# PART1.net
KiCad netlist of a schematic drawn in Altium Designer
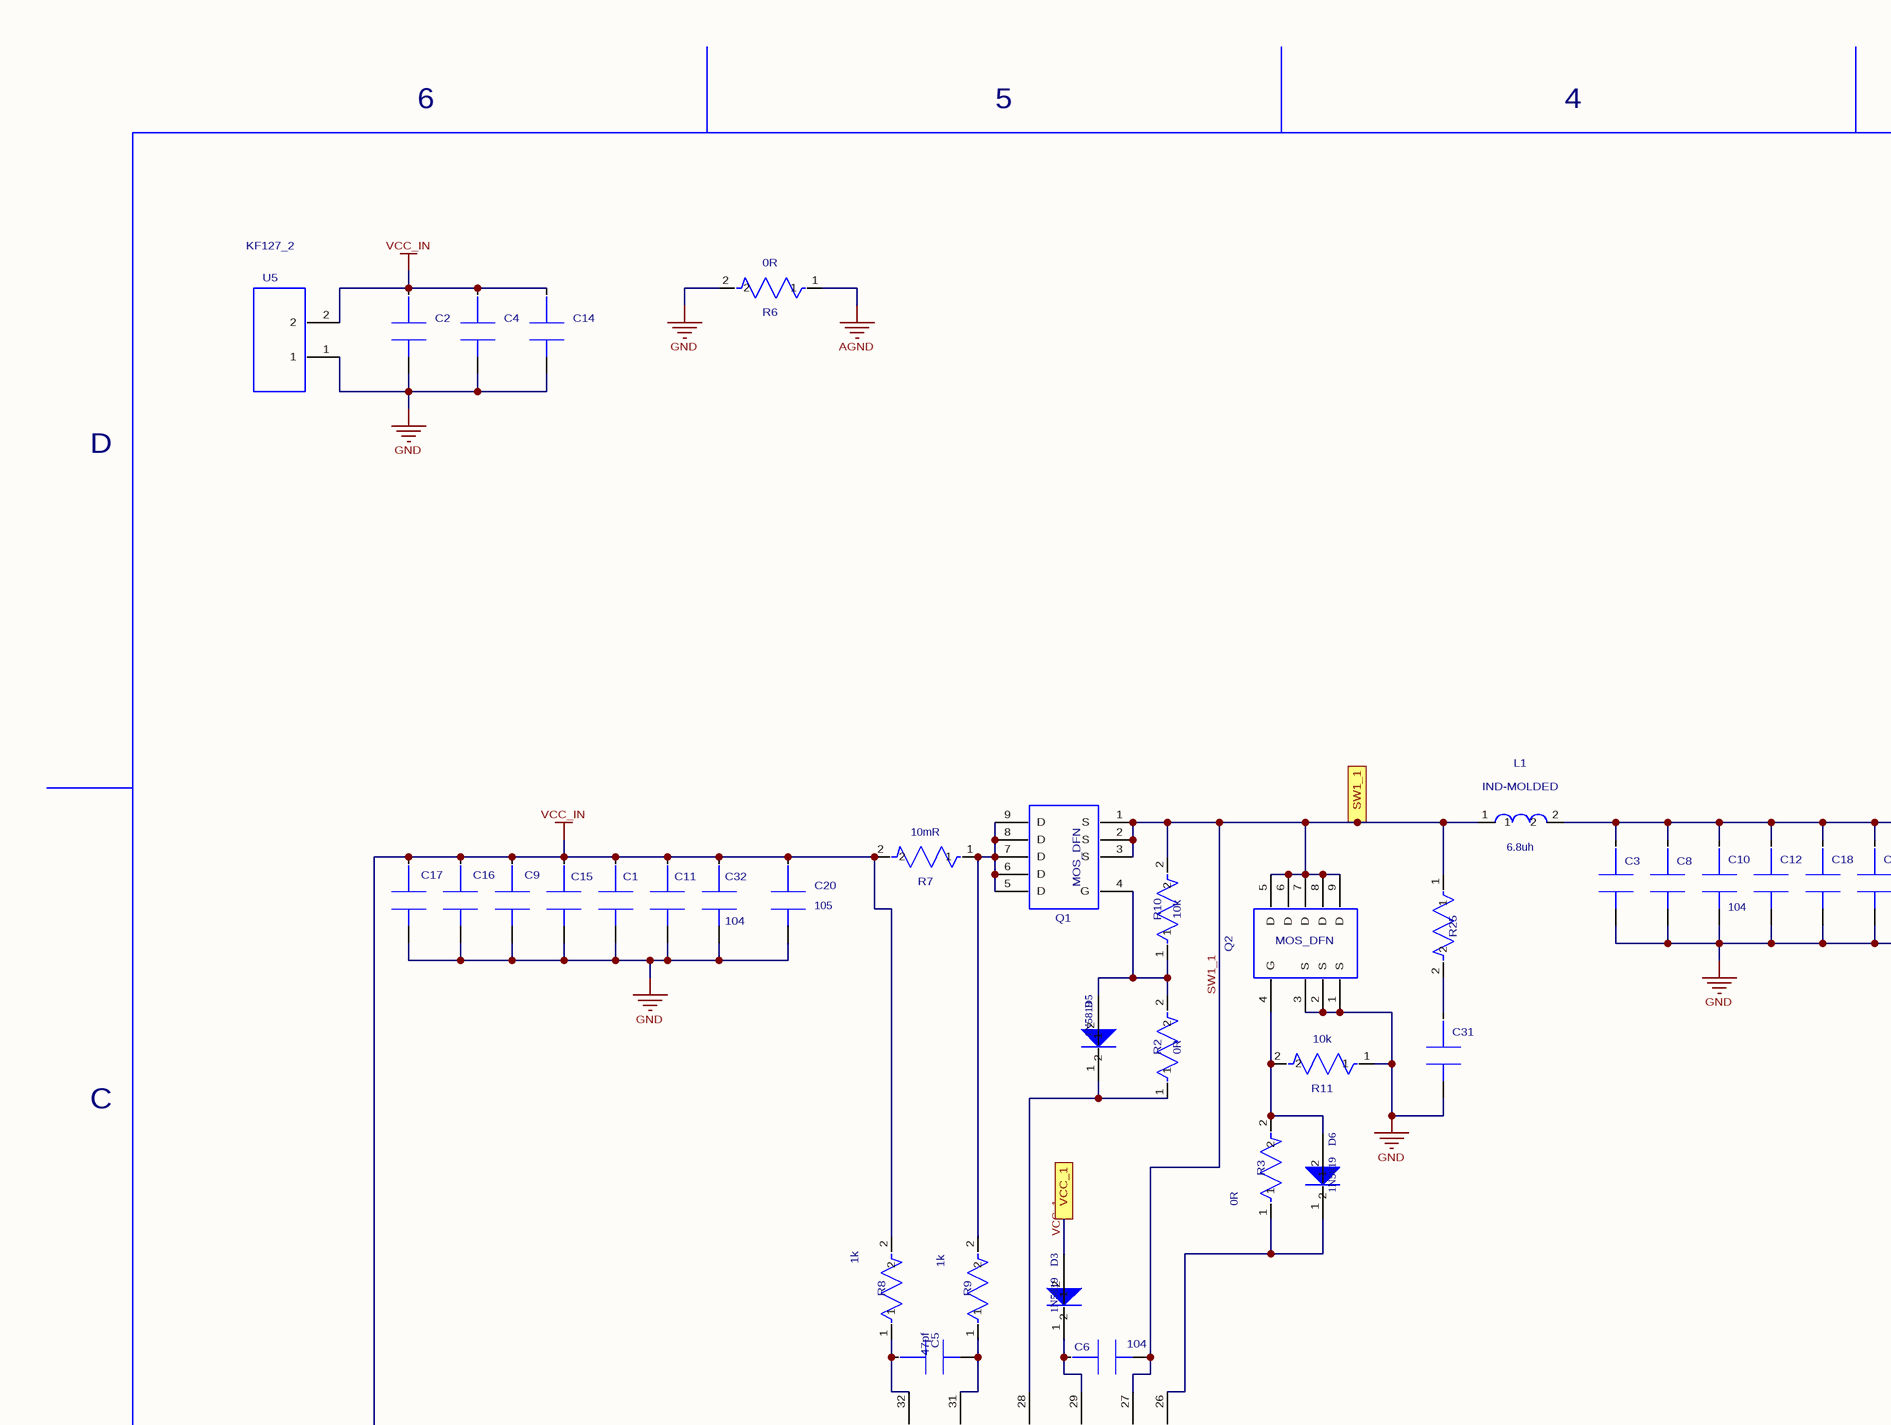
[diagram p0: PART1.SchDoc, top left]
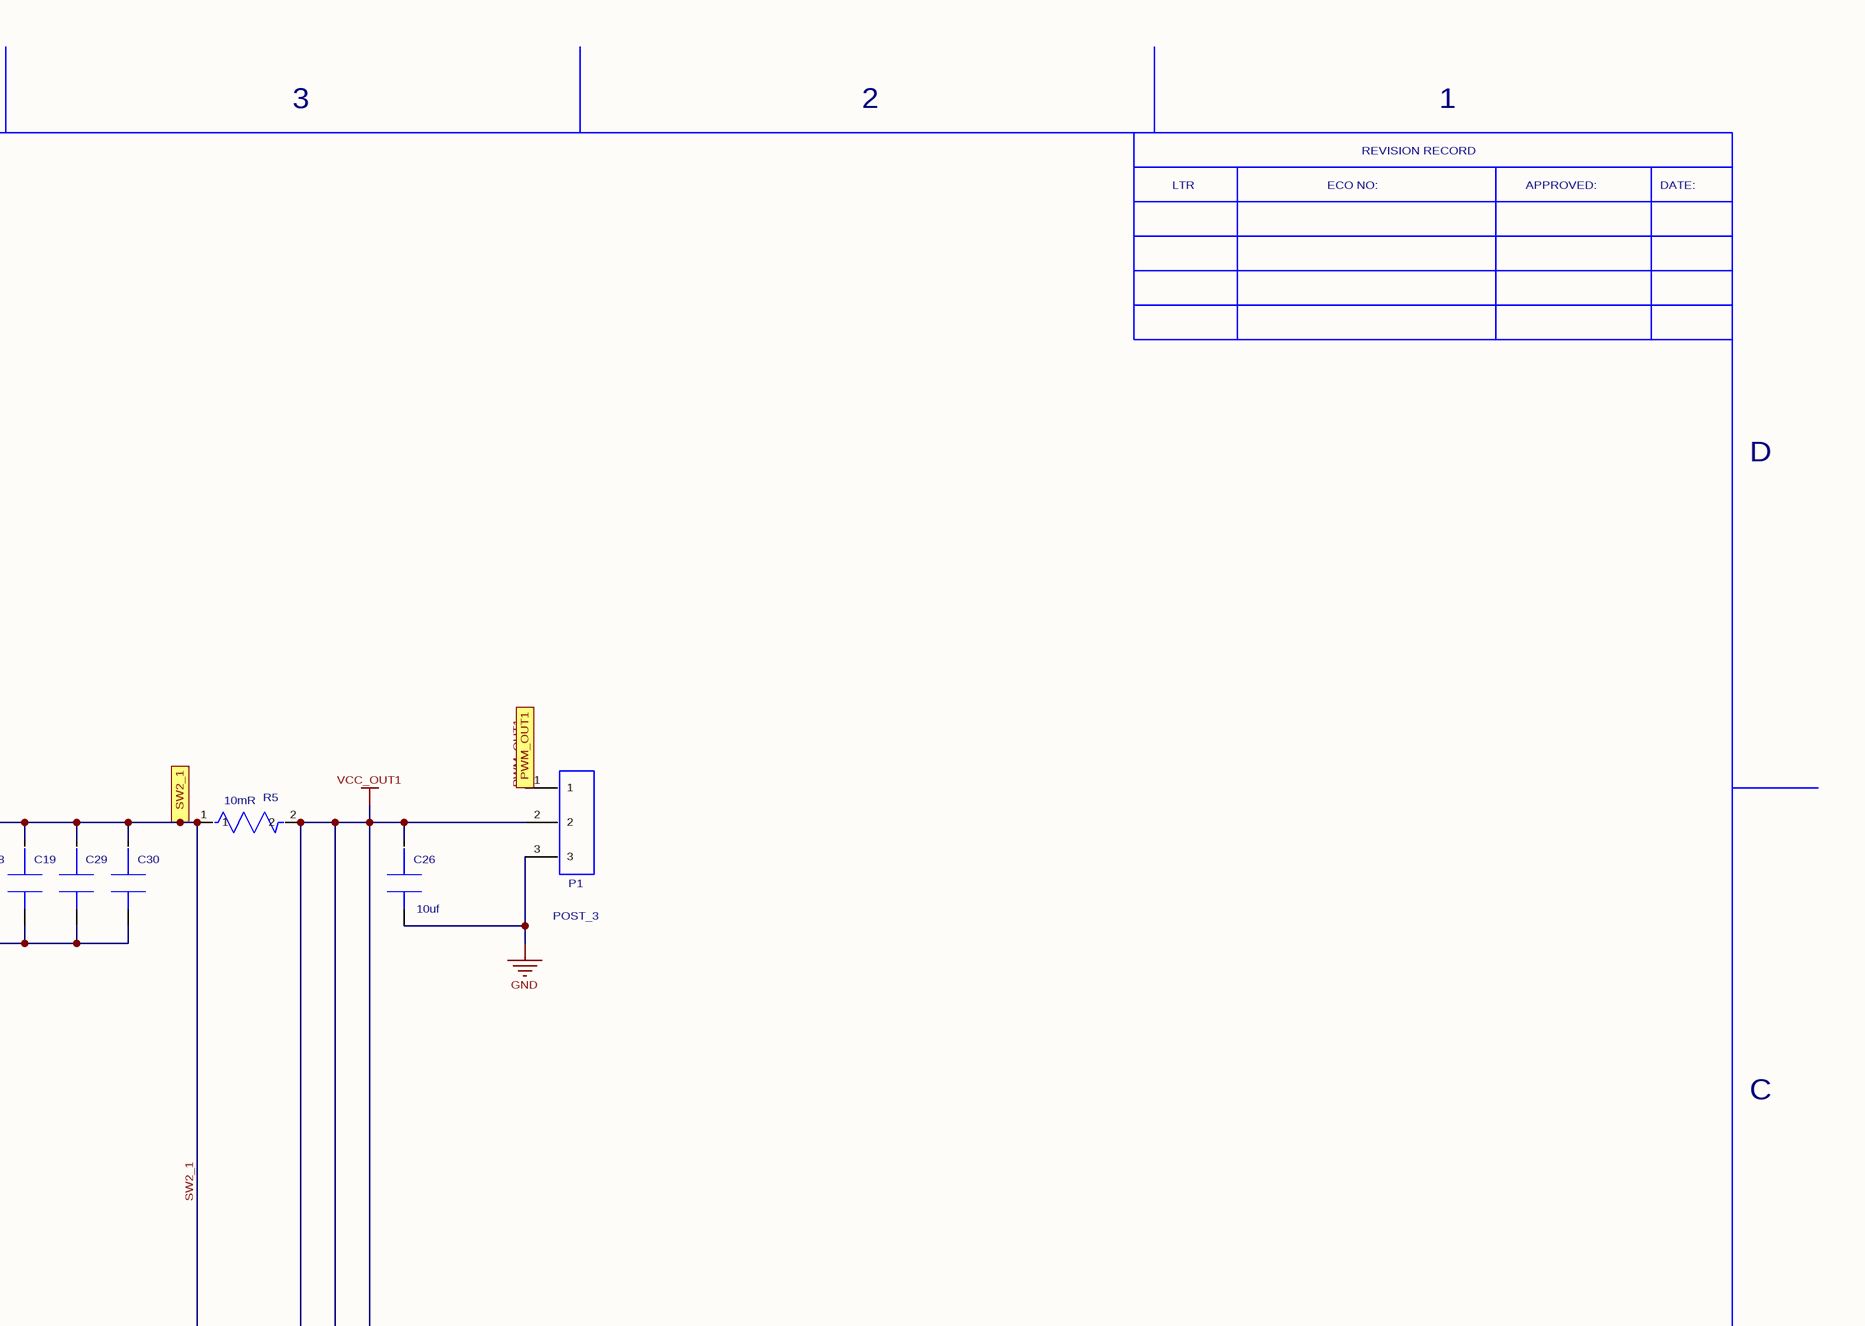
[diagram p1: PART1.SchDoc, top right]
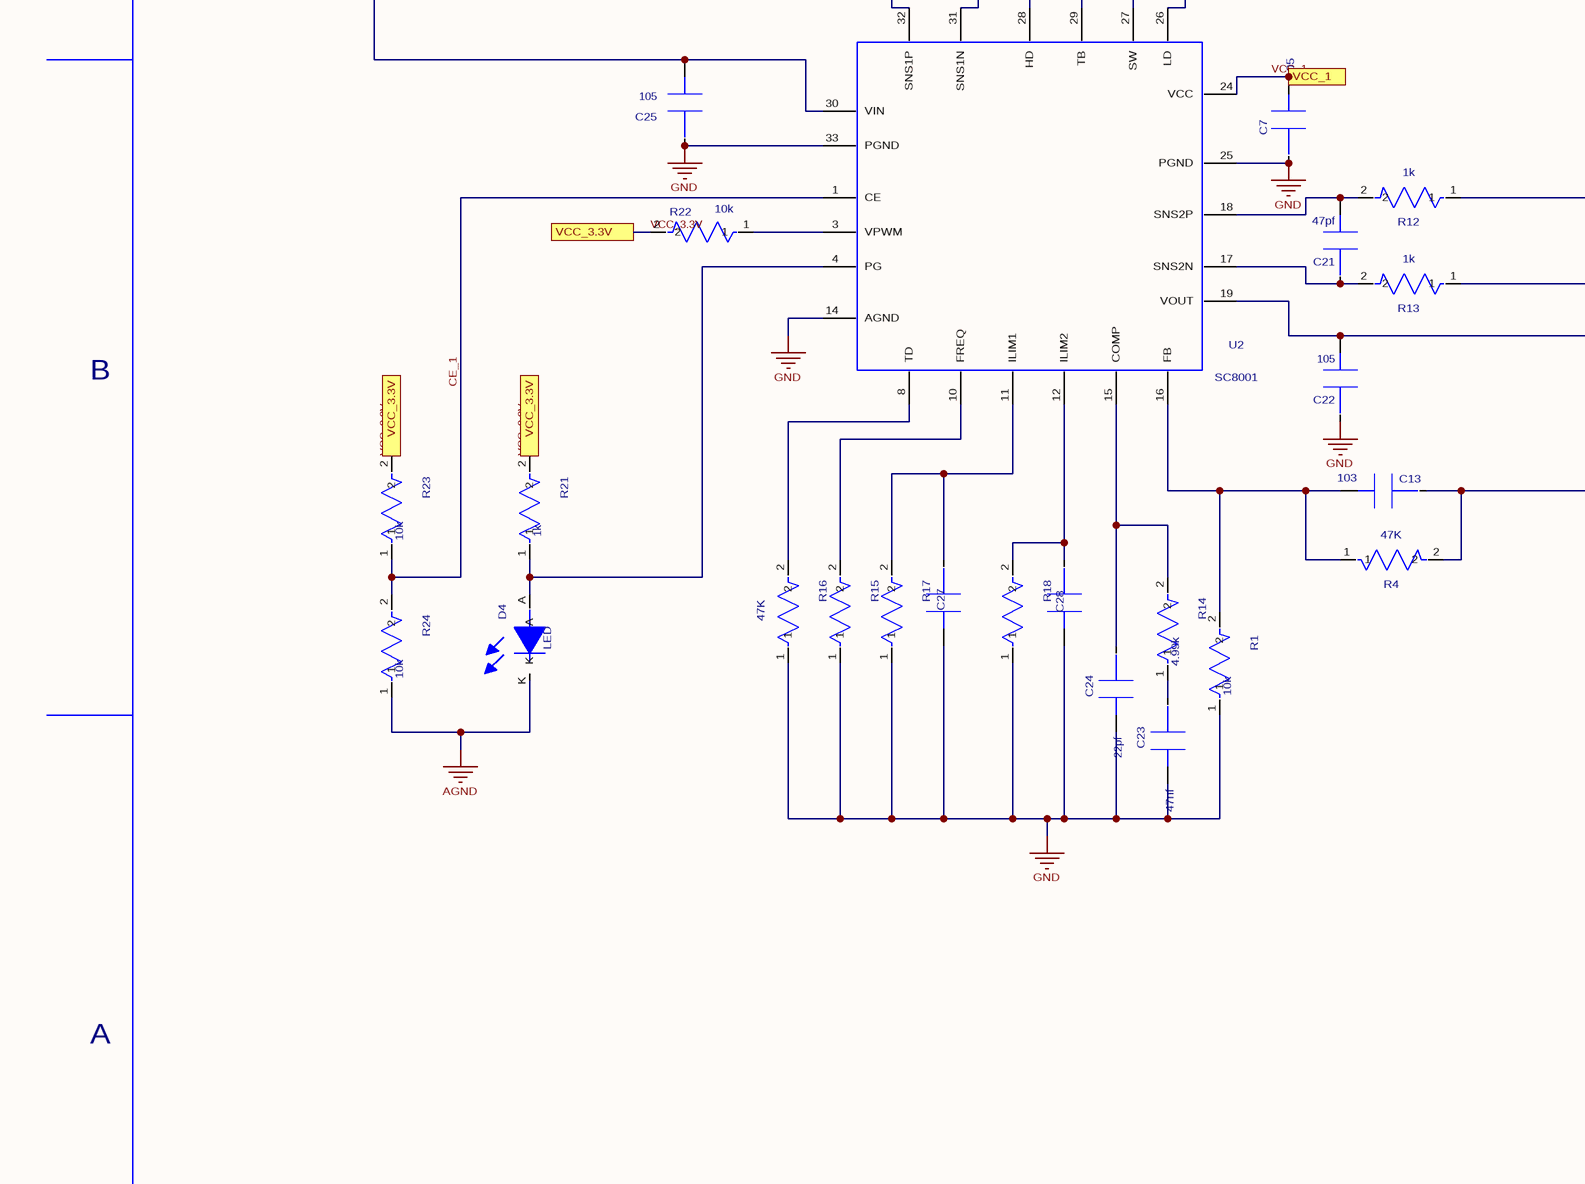
[diagram p2: PART1.SchDoc, bottom left]
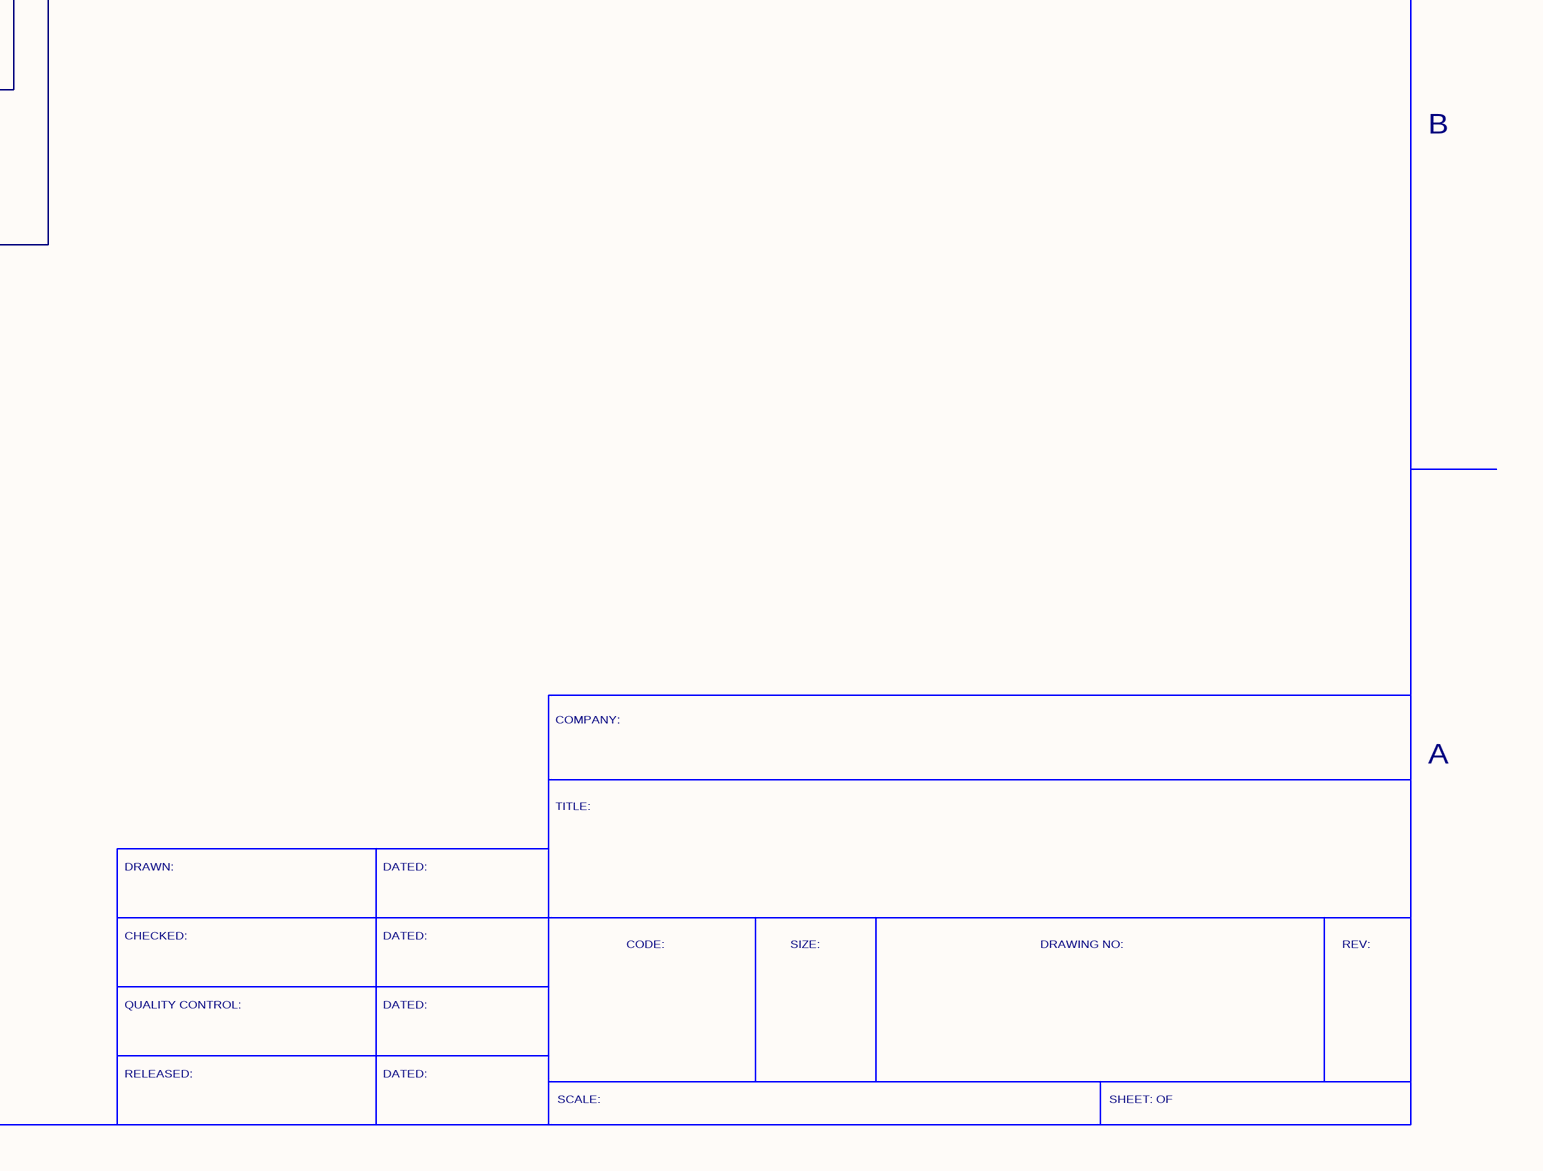
[diagram p3: PART1.SchDoc, bottom right]

(export (version "E")
  (design (tool "Eeschema 10.0.6"))
  (components
    (comp (ref "C1")
      (value "CAP-CFR04R-C")
      (footprint "1210C")
      (description "RADIAL FILM CAPACITOR, MIL-SPEC SIZE CFR04R SIZE 'C'")
      (fields (field (name "TOLERANCE") "???") (field (name "PART NUMBER") "TBD"))
      (libsource (lib "*") (part "CAP-CFR04R-C"))
    )
    (comp (ref "C2")
      (value "CAP-AE6.3")
      (footprint "CM_E(8_10.2)")
      (description "ALUMINUM ELECTROLYTIC CAP.")
      (libsource (lib "*") (part "CAP-AE6.3"))
    )
    (comp (ref "C3")
      (value "CAP-AE6.3")
      (footprint "CC6.56.5")
      (description "ALUMINUM ELECTROLYTIC CAP.")
      (libsource (lib "*") (part "CAP-AE6.3"))
    )
    (comp (ref "C4")
      (value "CAP-AE6.3")
      (footprint "CM_E(8_10.2)")
      (description "ALUMINUM ELECTROLYTIC CAP.")
      (libsource (lib "*") (part "CAP-AE6.3"))
    )
    (comp (ref "C5")
      (value "47pf")
      (footprint "0603C")
      (description "RADIAL FILM CAPACITOR, MIL-SPEC SIZE CFR04R SIZE 'C'")
      (fields (field (name "TOLERANCE") "???") (field (name "PART NUMBER") "TBD"))
      (libsource (lib "*") (part "CAP-CFR04R-C"))
    )
    (comp (ref "C6")
      (value "104")
      (footprint "0805C")
      (description "RADIAL FILM CAPACITOR, MIL-SPEC SIZE CFR04R SIZE 'C'")
      (fields (field (name "TOLERANCE") "???") (field (name "PART NUMBER") "TBD"))
      (libsource (lib "*") (part "CAP-CFR04R-C"))
    )
    (comp (ref "C7")
      (value "105")
      (footprint "0805C")
      (description "RADIAL FILM CAPACITOR, MIL-SPEC SIZE CFR04R SIZE 'C'")
      (fields (field (name "TOLERANCE") "???") (field (name "PART NUMBER") "TBD"))
      (libsource (lib "*") (part "CAP-CFR04R-C"))
    )
    (comp (ref "C8")
      (value "CAP-AE6.3")
      (footprint "CC6.56.5")
      (description "ALUMINUM ELECTROLYTIC CAP.")
      (libsource (lib "*") (part "CAP-AE6.3"))
    )
    (comp (ref "C9")
      (value "CAP-CFR04R-C")
      (footprint "1210C")
      (description "RADIAL FILM CAPACITOR, MIL-SPEC SIZE CFR04R SIZE 'C'")
      (fields (field (name "TOLERANCE") "???") (field (name "PART NUMBER") "TBD"))
      (libsource (lib "*") (part "CAP-CFR04R-C"))
    )
    (comp (ref "C10")
      (value "104")
      (footprint "1206C")
      (description "RADIAL FILM CAPACITOR, MIL-SPEC SIZE CFR04R SIZE 'C'")
      (fields (field (name "TOLERANCE") "???") (field (name "PART NUMBER") "TBD"))
      (libsource (lib "*") (part "CAP-CFR04R-C"))
    )
    (comp (ref "C11")
      (value "CAP-CFR04R-C")
      (footprint "1210C")
      (description "RADIAL FILM CAPACITOR, MIL-SPEC SIZE CFR04R SIZE 'C'")
      (fields (field (name "TOLERANCE") "???") (field (name "PART NUMBER") "TBD"))
      (libsource (lib "*") (part "CAP-CFR04R-C"))
    )
    (comp (ref "C12")
      (value "CAP-CFR04R-C")
      (footprint "1206C")
      (description "RADIAL FILM CAPACITOR, MIL-SPEC SIZE CFR04R SIZE 'C'")
      (fields (field (name "TOLERANCE") "???") (field (name "PART NUMBER") "TBD"))
      (libsource (lib "*") (part "CAP-CFR04R-C"))
    )
    (comp (ref "C13")
      (value "103")
      (footprint "0603C")
      (description "RADIAL FILM CAPACITOR, MIL-SPEC SIZE CFR04R SIZE 'C'")
      (fields (field (name "TOLERANCE") "???") (field (name "PART NUMBER") "TBD"))
      (libsource (lib "*") (part "CAP-CFR04R-C"))
    )
    (comp (ref "C14")
      (value "CAP-AE6.3")
      (footprint "CM_E(8_10.2)")
      (description "ALUMINUM ELECTROLYTIC CAP.")
      (libsource (lib "*") (part "CAP-AE6.3"))
    )
    (comp (ref "C15")
      (value "CAP-CFR04R-C")
      (footprint "1210C")
      (description "RADIAL FILM CAPACITOR, MIL-SPEC SIZE CFR04R SIZE 'C'")
      (fields (field (name "TOLERANCE") "???") (field (name "PART NUMBER") "TBD"))
      (libsource (lib "*") (part "CAP-CFR04R-C"))
    )
    (comp (ref "C16")
      (value "CAP-CFR04R-C")
      (footprint "1206C")
      (description "RADIAL FILM CAPACITOR, MIL-SPEC SIZE CFR04R SIZE 'C'")
      (fields (field (name "TOLERANCE") "???") (field (name "PART NUMBER") "TBD"))
      (libsource (lib "*") (part "CAP-CFR04R-C"))
    )
    (comp (ref "C17")
      (value "CAP-CFR04R-C")
      (footprint "1210C")
      (description "RADIAL FILM CAPACITOR, MIL-SPEC SIZE CFR04R SIZE 'C'")
      (fields (field (name "TOLERANCE") "???") (field (name "PART NUMBER") "TBD"))
      (libsource (lib "*") (part "CAP-CFR04R-C"))
    )
    (comp (ref "C18")
      (value "CAP-CFR04R-C")
      (footprint "1206C")
      (description "RADIAL FILM CAPACITOR, MIL-SPEC SIZE CFR04R SIZE 'C'")
      (fields (field (name "TOLERANCE") "???") (field (name "PART NUMBER") "TBD"))
      (libsource (lib "*") (part "CAP-CFR04R-C"))
    )
    (comp (ref "C19")
      (value "CAP-CFR04R-C")
      (footprint "1206C")
      (description "RADIAL FILM CAPACITOR, MIL-SPEC SIZE CFR04R SIZE 'C'")
      (fields (field (name "TOLERANCE") "???") (field (name "PART NUMBER") "TBD"))
      (libsource (lib "*") (part "CAP-CFR04R-C"))
    )
    (comp (ref "C20")
      (value "105")
      (footprint "0805C")
      (description "RADIAL FILM CAPACITOR, MIL-SPEC SIZE CFR04R SIZE 'C'")
      (fields (field (name "TOLERANCE") "???") (field (name "PART NUMBER") "TBD"))
      (libsource (lib "*") (part "CAP-CFR04R-C"))
    )
    (comp (ref "C21")
      (value "47pf")
      (footprint "0603C")
      (description "RADIAL FILM CAPACITOR, MIL-SPEC SIZE CFR04R SIZE 'C'")
      (fields (field (name "TOLERANCE") "???") (field (name "PART NUMBER") "TBD"))
      (libsource (lib "*") (part "CAP-CFR04R-C"))
    )
    (comp (ref "C22")
      (value "105")
      (footprint "0805C")
      (description "RADIAL FILM CAPACITOR, MIL-SPEC SIZE CFR04R SIZE 'C'")
      (fields (field (name "TOLERANCE") "???") (field (name "PART NUMBER") "TBD"))
      (libsource (lib "*") (part "CAP-CFR04R-C"))
    )
    (comp (ref "C23")
      (value "47nf")
      (footprint "0603C")
      (description "RADIAL FILM CAPACITOR, MIL-SPEC SIZE CFR04R SIZE 'C'")
      (fields (field (name "TOLERANCE") "???") (field (name "PART NUMBER") "TBD"))
      (libsource (lib "*") (part "CAP-CFR04R-C"))
    )
    (comp (ref "C24")
      (value "22pf")
      (footprint "0603C")
      (description "RADIAL FILM CAPACITOR, MIL-SPEC SIZE CFR04R SIZE 'C'")
      (fields (field (name "TOLERANCE") "???") (field (name "PART NUMBER") "TBD"))
      (libsource (lib "*") (part "CAP-CFR04R-C"))
    )
    (comp (ref "C25")
      (value "105")
      (footprint "0805C")
      (description "RADIAL FILM CAPACITOR, MIL-SPEC SIZE CFR04R SIZE 'C'")
      (fields (field (name "TOLERANCE") "???") (field (name "PART NUMBER") "TBD"))
      (libsource (lib "*") (part "CAP-CFR04R-C"))
    )
    (comp (ref "C26")
      (value "10uf")
      (footprint "1206C")
      (description "RADIAL FILM CAPACITOR, MIL-SPEC SIZE CFR04R SIZE 'C'")
      (fields (field (name "TOLERANCE") "???") (field (name "PART NUMBER") "TBD"))
      (libsource (lib "*") (part "CAP-CFR04R-C"))
    )
    (comp (ref "C27")
      (value "CAP-CFR04R-C")
      (footprint "0603C")
      (description "RADIAL FILM CAPACITOR, MIL-SPEC SIZE CFR04R SIZE 'C'")
      (fields (field (name "TOLERANCE") "???") (field (name "PART NUMBER") "TBD"))
      (libsource (lib "*") (part "CAP-CFR04R-C"))
    )
    (comp (ref "C28")
      (value "CAP-CFR04R-C")
      (footprint "0603C")
      (description "RADIAL FILM CAPACITOR, MIL-SPEC SIZE CFR04R SIZE 'C'")
      (fields (field (name "TOLERANCE") "???") (field (name "PART NUMBER") "TBD"))
      (libsource (lib "*") (part "CAP-CFR04R-C"))
    )
    (comp (ref "C29")
      (value "CAP-CFR04R-C")
      (footprint "1206C")
      (description "RADIAL FILM CAPACITOR, MIL-SPEC SIZE CFR04R SIZE 'C'")
      (fields (field (name "TOLERANCE") "???") (field (name "PART NUMBER") "TBD"))
      (libsource (lib "*") (part "CAP-CFR04R-C"))
    )
    (comp (ref "C30")
      (value "CAP-CFR04R-C")
      (footprint "1206C")
      (description "RADIAL FILM CAPACITOR, MIL-SPEC SIZE CFR04R SIZE 'C'")
      (fields (field (name "TOLERANCE") "???") (field (name "PART NUMBER") "TBD"))
      (libsource (lib "*") (part "CAP-CFR04R-C"))
    )
    (comp (ref "C31")
      (value "CAP-CFR04R-C")
      (footprint "0805C")
      (description "RADIAL FILM CAPACITOR, MIL-SPEC SIZE CFR04R SIZE 'C'")
      (fields (field (name "TOLERANCE") "???") (field (name "PART NUMBER") "TBD"))
      (libsource (lib "*") (part "CAP-CFR04R-C"))
    )
    (comp (ref "C32")
      (value "104")
      (footprint "0805C")
      (description "RADIAL FILM CAPACITOR, MIL-SPEC SIZE CFR04R SIZE 'C'")
      (fields (field (name "TOLERANCE") "???") (field (name "PART NUMBER") "TBD"))
      (libsource (lib "*") (part "CAP-CFR04R-C"))
    )
    (comp (ref "D3")
      (value "1N5819")
      (footprint "SOD-123_L2.8-W1.8-LS3.7-RD")
      (description "High Conductance Fast Diode")
      (fields (field (name "PUBLISHER") "Altium Limited"))
      (libsource (lib "*") (part "DIODE_1N4148"))
    )
    (comp (ref "D4")
      (value "LED")
      (footprint "0805D")
      (description "LIGHT EMITTING DIODE")
      (libsource (lib "*") (part "LED"))
    )
    (comp (ref "D5")
      (value "1N5819")
      (footprint "SOD-123_L2.8-W1.8-LS3.7-RD")
      (description "High Conductance Fast Diode")
      (fields (field (name "PUBLISHER") "Altium Limited"))
      (libsource (lib "*") (part "DIODE_1N4148"))
    )
    (comp (ref "D6")
      (value "1N5819")
      (footprint "SOD-123_L2.8-W1.8-LS3.7-RD")
      (description "High Conductance Fast Diode")
      (fields (field (name "PUBLISHER") "Altium Limited"))
      (libsource (lib "*") (part "DIODE_1N4148"))
    )
    (comp (ref "L1")
      (value "IND-MOLDED")
      (footprint "1040L")
      (description "MOLDED INDUCTOR, 0.5\" PIN SPACING")
      (fields (field (name "ALTIUM_VALUE") "6.8uh"))
      (libsource (lib "*") (part "IND-MOLDED"))
    )
    (comp (ref "P1") (value "POST_3") (footprint "POST_3") (libsource (lib "*") (part "POST_3")))
    (comp (ref "Q1") (value "MOS_DFN") (footprint "DFN-8_5X6") (libsource (lib "*") (part "MOS_DFN")))
    (comp (ref "Q2") (value "MOS_DFN") (footprint "DFN-8_5X6") (libsource (lib "*") (part "MOS_DFN")))
    (comp (ref "R1")
      (value "10k")
      (footprint "0603R")
      (description "WIRE WOUND RESISTOR 3.4 X 7.05 MM")
      (fields (field (name "Comment") "RES-WR1"))
      (libsource (lib "*") (part "RES-WR1"))
    )
    (comp (ref "R2")
      (value "0R")
      (footprint "0603R")
      (description "WIRE WOUND RESISTOR 3.4 X 7.05 MM")
      (fields (field (name "Comment") "RES-WR1"))
      (libsource (lib "*") (part "RES-WR1"))
    )
    (comp (ref "R3")
      (value "0R")
      (footprint "0603R")
      (description "WIRE WOUND RESISTOR 3.4 X 7.05 MM")
      (fields (field (name "Comment") "RES-WR1"))
      (libsource (lib "*") (part "RES-WR1"))
    )
    (comp (ref "R4")
      (value "47K")
      (footprint "0603R")
      (description "WIRE WOUND RESISTOR 3.4 X 7.05 MM")
      (fields (field (name "Comment") "RES-WR1"))
      (libsource (lib "*") (part "RES-WR1"))
    )
    (comp (ref "R5")
      (value "10mR")
      (footprint "1206C")
      (description "WIRE WOUND RESISTOR 3.4 X 7.05 MM")
      (fields (field (name "Comment") "RES-WR1"))
      (libsource (lib "*") (part "RES-WR1"))
    )
    (comp (ref "R6")
      (value "0R")
      (footprint "1206C")
      (description "WIRE WOUND RESISTOR 3.4 X 7.05 MM")
      (fields (field (name "Comment") "RES-WR1"))
      (libsource (lib "*") (part "RES-WR1"))
    )
    (comp (ref "R7")
      (value "10mR")
      (footprint "1206C")
      (description "WIRE WOUND RESISTOR 3.4 X 7.05 MM")
      (fields (field (name "Comment") "RES-WR1"))
      (libsource (lib "*") (part "RES-WR1"))
    )
    (comp (ref "R8")
      (value "1k")
      (footprint "0603R")
      (description "WIRE WOUND RESISTOR 3.4 X 7.05 MM")
      (fields (field (name "Comment") "RES-WR1"))
      (libsource (lib "*") (part "RES-WR1"))
    )
    (comp (ref "R9")
      (value "1k")
      (footprint "0603R")
      (description "WIRE WOUND RESISTOR 3.4 X 7.05 MM")
      (fields (field (name "Comment") "RES-WR1"))
      (libsource (lib "*") (part "RES-WR1"))
    )
    (comp (ref "R10")
      (value "10k")
      (footprint "0603R")
      (description "WIRE WOUND RESISTOR 3.4 X 7.05 MM")
      (fields (field (name "Comment") "RES-WR1"))
      (libsource (lib "*") (part "RES-WR1"))
    )
    (comp (ref "R11")
      (value "10k")
      (footprint "0603R")
      (description "WIRE WOUND RESISTOR 3.4 X 7.05 MM")
      (fields (field (name "Comment") "RES-WR1"))
      (libsource (lib "*") (part "RES-WR1"))
    )
    (comp (ref "R12")
      (value "1k")
      (footprint "0603R")
      (description "WIRE WOUND RESISTOR 3.4 X 7.05 MM")
      (fields (field (name "Comment") "RES-WR1"))
      (libsource (lib "*") (part "RES-WR1"))
    )
    (comp (ref "R13")
      (value "1k")
      (footprint "0603R")
      (description "WIRE WOUND RESISTOR 3.4 X 7.05 MM")
      (fields (field (name "Comment") "RES-WR1"))
      (libsource (lib "*") (part "RES-WR1"))
    )
    (comp (ref "R14")
      (value "4.99k")
      (footprint "0603R")
      (description "WIRE WOUND RESISTOR 3.4 X 7.05 MM")
      (fields (field (name "Comment") "RES-WR1"))
      (libsource (lib "*") (part "RES-WR1"))
    )
    (comp (ref "R15")
      (value "RES-WR1")
      (footprint "0603R")
      (description "WIRE WOUND RESISTOR 3.4 X 7.05 MM")
      (libsource (lib "*") (part "RES-WR1"))
    )
    (comp (ref "R16")
      (value "47K")
      (footprint "0603R")
      (description "WIRE WOUND RESISTOR 3.4 X 7.05 MM")
      (libsource (lib "*") (part "RES-WR1"))
    )
    (comp (ref "R17")
      (value "RES-WR1")
      (footprint "0603R")
      (description "WIRE WOUND RESISTOR 3.4 X 7.05 MM")
      (libsource (lib "*") (part "RES-WR1"))
    )
    (comp (ref "R18")
      (value "39k")
      (footprint "0603R")
      (description "WIRE WOUND RESISTOR 3.4 X 7.05 MM")
      (libsource (lib "*") (part "RES-WR1"))
    )
    (comp (ref "R21")
      (value "1k")
      (footprint "0805R")
      (description "WIRE WOUND RESISTOR 3.4 X 7.05 MM")
      (fields (field (name "Comment") "RES-WR1"))
      (libsource (lib "*") (part "RES-WR1"))
    )
    (comp (ref "R22")
      (value "10k")
      (footprint "0805R")
      (description "WIRE WOUND RESISTOR 3.4 X 7.05 MM")
      (fields (field (name "Comment") "RES-WR1"))
      (libsource (lib "*") (part "RES-WR1"))
    )
    (comp (ref "R23")
      (value "10k")
      (footprint "0805R")
      (description "WIRE WOUND RESISTOR 3.4 X 7.05 MM")
      (fields (field (name "Comment") "RES-WR1"))
      (libsource (lib "*") (part "RES-WR1"))
    )
    (comp (ref "R24")
      (value "10k")
      (footprint "0805R")
      (description "WIRE WOUND RESISTOR 3.4 X 7.05 MM")
      (fields (field (name "Comment") "RES-WR1"))
      (libsource (lib "*") (part "RES-WR1"))
    )
    (comp (ref "R25")
      (value "RES-WR1")
      (footprint "1206C")
      (description "WIRE WOUND RESISTOR 3.4 X 7.05 MM")
      (libsource (lib "*") (part "RES-WR1"))
    )
    (comp (ref "U2")
      (value "SC8001")
      (footprint "QFN-32_L4.0-W4.0-P0.40-BL-EP2.7")
      (libsource (lib "*") (part "SC8001"))
    )
    (comp (ref "U5") (value "KF127_2") (footprint "KF127_2") (libsource (lib "*") (part "KF127_2")))
  )
  (nets
    (net (code "1") (name "/CE_1") (class "Default")
      (node (ref "R23") (pin "1") (pinfunction "1_1") (pintype "passive"))
      (node (ref "R24") (pin "2") (pinfunction "2_2") (pintype "passive"))
      (node (ref "U2") (pin "1") (pinfunction "CE_1") (pintype "passive"))
    )
    (net (code "2") (name "/PWM_OUT1") (class "Default")
      (node (ref "P1") (pin "1") (pinfunction "1_1") (pintype "passive"))
    )
    (net (code "3") (name "/SW1_1") (class "Default")
      (node (ref "C6") (pin "2") (pinfunction "2_2") (pintype "passive"))
      (node (ref "L1") (pin "1") (pinfunction "1_1") (pintype "passive"))
      (node (ref "Q1") (pin "1") (pinfunction "S_1") (pintype "passive"))
      (node (ref "Q1") (pin "2") (pinfunction "S_2") (pintype "passive"))
      (node (ref "Q1") (pin "3") (pinfunction "S_3") (pintype "passive"))
      (node (ref "Q2") (pin "5") (pinfunction "D_5") (pintype "passive"))
      (node (ref "Q2") (pin "6") (pinfunction "D_6") (pintype "passive"))
      (node (ref "Q2") (pin "7") (pinfunction "D_7") (pintype "passive"))
      (node (ref "Q2") (pin "8") (pinfunction "D_8") (pintype "passive"))
      (node (ref "Q2") (pin "9") (pinfunction "D_9") (pintype "passive"))
      (node (ref "R10") (pin "2") (pinfunction "2_2") (pintype "passive"))
      (node (ref "R25") (pin "1") (pinfunction "1_1") (pintype "passive"))
      (node (ref "U2") (pin "27") (pinfunction "SW_27") (pintype "passive"))
    )
    (net (code "4") (name "/SW2_1") (class "Default")
      (node (ref "C10") (pin "1") (pinfunction "1_1") (pintype "passive"))
      (node (ref "C12") (pin "1") (pinfunction "1_1") (pintype "passive"))
      (node (ref "C18") (pin "1") (pinfunction "1_1") (pintype "passive"))
      (node (ref "C19") (pin "1") (pinfunction "1_1") (pintype "passive"))
      (node (ref "C29") (pin "1") (pinfunction "1_1") (pintype "passive"))
      (node (ref "C3") (pin "1") (pinfunction "1_1") (pintype "passive"))
      (node (ref "C30") (pin "1") (pinfunction "1_1") (pintype "passive"))
      (node (ref "C8") (pin "1") (pinfunction "1_1") (pintype "passive"))
      (node (ref "L1") (pin "2") (pinfunction "2_2") (pintype "passive"))
      (node (ref "R12") (pin "1") (pinfunction "1_1") (pintype "passive"))
      (node (ref "R5") (pin "1") (pinfunction "1_1") (pintype "passive"))
    )
    (net (code "5") (name "/VCC_1") (class "Default")
      (node (ref "C7") (pin "2") (pinfunction "2_2") (pintype "passive"))
      (node (ref "D3") (pin "2") (pinfunction "2_2") (pintype "passive"))
      (node (ref "U2") (pin "24") (pinfunction "VCC_24") (pintype "passive"))
    )
    (net (code "6") (name "/VCC_3.3V") (class "Default")
      (node (ref "R21") (pin "2") (pinfunction "2_2") (pintype "passive"))
      (node (ref "R22") (pin "2") (pinfunction "2_2") (pintype "passive"))
      (node (ref "R23") (pin "2") (pinfunction "2_2") (pintype "passive"))
    )
    (net (code "7") (name "AGND") (class "Default")
      (node (ref "D4") (pin "K") (pinfunction "K_K") (pintype "passive"))
      (node (ref "R24") (pin "1") (pinfunction "1_1") (pintype "passive"))
      (node (ref "R6") (pin "1") (pinfunction "1_1") (pintype "passive"))
    )
    (net (code "8") (name "GND") (class "Default")
      (node (ref "C1") (pin "2") (pinfunction "2_2") (pintype "passive"))
      (node (ref "C10") (pin "2") (pinfunction "2_2") (pintype "passive"))
      (node (ref "C11") (pin "2") (pinfunction "2_2") (pintype "passive"))
      (node (ref "C12") (pin "2") (pinfunction "2_2") (pintype "passive"))
      (node (ref "C14") (pin "2") (pinfunction "2_2") (pintype "passive"))
      (node (ref "C15") (pin "2") (pinfunction "2_2") (pintype "passive"))
      (node (ref "C16") (pin "2") (pinfunction "2_2") (pintype "passive"))
      (node (ref "C17") (pin "2") (pinfunction "2_2") (pintype "passive"))
      (node (ref "C18") (pin "2") (pinfunction "2_2") (pintype "passive"))
      (node (ref "C19") (pin "2") (pinfunction "2_2") (pintype "passive"))
      (node (ref "C2") (pin "2") (pinfunction "2_2") (pintype "passive"))
      (node (ref "C20") (pin "2") (pinfunction "2_2") (pintype "passive"))
      (node (ref "C22") (pin "1") (pinfunction "1_1") (pintype "passive"))
      (node (ref "C23") (pin "2") (pinfunction "2_2") (pintype "passive"))
      (node (ref "C24") (pin "2") (pinfunction "2_2") (pintype "passive"))
      (node (ref "C25") (pin "1") (pinfunction "1_1") (pintype "passive"))
      (node (ref "C26") (pin "2") (pinfunction "2_2") (pintype "passive"))
      (node (ref "C27") (pin "2") (pinfunction "2_2") (pintype "passive"))
      (node (ref "C28") (pin "2") (pinfunction "2_2") (pintype "passive"))
      (node (ref "C29") (pin "2") (pinfunction "2_2") (pintype "passive"))
      (node (ref "C3") (pin "2") (pinfunction "2_2") (pintype "passive"))
      (node (ref "C30") (pin "2") (pinfunction "2_2") (pintype "passive"))
      (node (ref "C31") (pin "2") (pinfunction "2_2") (pintype "passive"))
      (node (ref "C32") (pin "2") (pinfunction "2_2") (pintype "passive"))
      (node (ref "C4") (pin "2") (pinfunction "2_2") (pintype "passive"))
      (node (ref "C7") (pin "1") (pinfunction "1_1") (pintype "passive"))
      (node (ref "C8") (pin "2") (pinfunction "2_2") (pintype "passive"))
      (node (ref "C9") (pin "2") (pinfunction "2_2") (pintype "passive"))
      (node (ref "P1") (pin "3") (pinfunction "3_3") (pintype "passive"))
      (node (ref "Q2") (pin "1") (pinfunction "S_1") (pintype "passive"))
      (node (ref "Q2") (pin "2") (pinfunction "S_2") (pintype "passive"))
      (node (ref "Q2") (pin "3") (pinfunction "S_3") (pintype "passive"))
      (node (ref "R1") (pin "1") (pinfunction "1_1") (pintype "passive"))
      (node (ref "R11") (pin "1") (pinfunction "1_1") (pintype "passive"))
      (node (ref "R15") (pin "1") (pinfunction "1_1") (pintype "passive"))
      (node (ref "R16") (pin "1") (pinfunction "1_1") (pintype "passive"))
      (node (ref "R17") (pin "1") (pinfunction "1_1") (pintype "passive"))
      (node (ref "R18") (pin "1") (pinfunction "1_1") (pintype "passive"))
      (node (ref "R6") (pin "2") (pinfunction "2_2") (pintype "passive"))
      (node (ref "U2") (pin "14") (pinfunction "AGND_14") (pintype "passive"))
      (node (ref "U2") (pin "25") (pinfunction "PGND_25") (pintype "passive"))
      (node (ref "U2") (pin "33") (pinfunction "PGND_33") (pintype "passive"))
      (node (ref "U5") (pin "1") (pinfunction "1_1") (pintype "passive"))
    )
    (net (code "9") (name "Net-(C23-Pad1)") (class "Default")
      (node (ref "C23") (pin "1") (pinfunction "1_1") (pintype "passive"))
      (node (ref "R14") (pin "1") (pinfunction "1_1") (pintype "passive"))
    )
    (net (code "10") (name "Net-(C31-Pad1)") (class "Default")
      (node (ref "C31") (pin "1") (pinfunction "1_1") (pintype "passive"))
      (node (ref "R25") (pin "2") (pinfunction "2_2") (pintype "passive"))
    )
    (net (code "11") (name "Net-(Q1-D-Pad5)") (class "Default")
      (node (ref "Q1") (pin "5") (pinfunction "D_5") (pintype "passive"))
      (node (ref "Q1") (pin "6") (pinfunction "D_6") (pintype "passive"))
      (node (ref "Q1") (pin "7") (pinfunction "D_7") (pintype "passive"))
      (node (ref "Q1") (pin "8") (pinfunction "D_8") (pintype "passive"))
      (node (ref "Q1") (pin "9") (pinfunction "D_9") (pintype "passive"))
      (node (ref "R7") (pin "1") (pinfunction "1_1") (pintype "passive"))
      (node (ref "R9") (pin "2") (pinfunction "2_2") (pintype "passive"))
    )
    (net (code "12") (name "Net-(Q1-G)") (class "Default")
      (node (ref "D5") (pin "2") (pinfunction "2_2") (pintype "passive"))
      (node (ref "Q1") (pin "4") (pinfunction "G_4") (pintype "passive"))
      (node (ref "R10") (pin "1") (pinfunction "1_1") (pintype "passive"))
      (node (ref "R2") (pin "2") (pinfunction "2_2") (pintype "passive"))
    )
    (net (code "13") (name "Net-(Q2-G)") (class "Default")
      (node (ref "D6") (pin "2") (pinfunction "2_2") (pintype "passive"))
      (node (ref "Q2") (pin "4") (pinfunction "G_4") (pintype "passive"))
      (node (ref "R11") (pin "2") (pinfunction "2_2") (pintype "passive"))
      (node (ref "R3") (pin "2") (pinfunction "2_2") (pintype "passive"))
    )
    (net (code "14") (name "Net-(U2-COMP)") (class "Default")
      (node (ref "C24") (pin "1") (pinfunction "1_1") (pintype "passive"))
      (node (ref "R14") (pin "2") (pinfunction "2_2") (pintype "passive"))
      (node (ref "U2") (pin "15") (pinfunction "COMP_15") (pintype "passive"))
    )
    (net (code "15") (name "Net-(U2-FB)") (class "Default")
      (node (ref "C13") (pin "2") (pinfunction "2_2") (pintype "passive"))
      (node (ref "R1") (pin "2") (pinfunction "2_2") (pintype "passive"))
      (node (ref "R4") (pin "1") (pinfunction "1_1") (pintype "passive"))
      (node (ref "U2") (pin "16") (pinfunction "FB_16") (pintype "passive"))
    )
    (net (code "16") (name "Net-(U2-FREQ)") (class "Default")
      (node (ref "R15") (pin "2") (pinfunction "2_2") (pintype "passive"))
      (node (ref "U2") (pin "10") (pinfunction "FREQ_10") (pintype "passive"))
    )
    (net (code "17") (name "Net-(U2-HD)") (class "Default")
      (node (ref "D5") (pin "1") (pinfunction "1_1") (pintype "passive"))
      (node (ref "R2") (pin "1") (pinfunction "1_1") (pintype "passive"))
      (node (ref "U2") (pin "28") (pinfunction "HD_28") (pintype "passive"))
    )
    (net (code "18") (name "Net-(U2-ILIM1)") (class "Default")
      (node (ref "C27") (pin "1") (pinfunction "1_1") (pintype "passive"))
      (node (ref "R17") (pin "2") (pinfunction "2_2") (pintype "passive"))
      (node (ref "U2") (pin "11") (pinfunction "ILIM1_11") (pintype "passive"))
    )
    (net (code "19") (name "Net-(U2-ILIM2)") (class "Default")
      (node (ref "C28") (pin "1") (pinfunction "1_1") (pintype "passive"))
      (node (ref "R18") (pin "2") (pinfunction "2_2") (pintype "passive"))
      (node (ref "U2") (pin "12") (pinfunction "ILIM2_12") (pintype "passive"))
    )
    (net (code "20") (name "Net-(U2-LD)") (class "Default")
      (node (ref "D6") (pin "1") (pinfunction "1_1") (pintype "passive"))
      (node (ref "R3") (pin "1") (pinfunction "1_1") (pintype "passive"))
      (node (ref "U2") (pin "26") (pinfunction "LD_26") (pintype "passive"))
    )
    (net (code "21") (name "Net-(U2-PG)") (class "Default")
      (node (ref "D4") (pin "A") (pinfunction "A_A") (pintype "passive"))
      (node (ref "R21") (pin "1") (pinfunction "1_1") (pintype "passive"))
      (node (ref "U2") (pin "4") (pinfunction "PG_4") (pintype "passive"))
    )
    (net (code "22") (name "Net-(U2-SNS1N)") (class "Default")
      (node (ref "C5") (pin "2") (pinfunction "2_2") (pintype "passive"))
      (node (ref "R9") (pin "1") (pinfunction "1_1") (pintype "passive"))
      (node (ref "U2") (pin "31") (pinfunction "SNS1N_31") (pintype "passive"))
    )
    (net (code "23") (name "Net-(U2-SNS1P)") (class "Default")
      (node (ref "C5") (pin "1") (pinfunction "1_1") (pintype "passive"))
      (node (ref "R8") (pin "1") (pinfunction "1_1") (pintype "passive"))
      (node (ref "U2") (pin "32") (pinfunction "SNS1P_32") (pintype "passive"))
    )
    (net (code "24") (name "Net-(U2-SNS2N)") (class "Default")
      (node (ref "C21") (pin "1") (pinfunction "1_1") (pintype "passive"))
      (node (ref "R13") (pin "2") (pinfunction "2_2") (pintype "passive"))
      (node (ref "U2") (pin "17") (pinfunction "SNS2N_17") (pintype "passive"))
    )
    (net (code "25") (name "Net-(U2-SNS2P)") (class "Default")
      (node (ref "C21") (pin "2") (pinfunction "2_2") (pintype "passive"))
      (node (ref "R12") (pin "2") (pinfunction "2_2") (pintype "passive"))
      (node (ref "U2") (pin "18") (pinfunction "SNS2P_18") (pintype "passive"))
    )
    (net (code "26") (name "Net-(U2-TB)") (class "Default")
      (node (ref "C6") (pin "1") (pinfunction "1_1") (pintype "passive"))
      (node (ref "D3") (pin "1") (pinfunction "1_1") (pintype "passive"))
      (node (ref "U2") (pin "29") (pinfunction "TB_29") (pintype "passive"))
    )
    (net (code "27") (name "Net-(U2-TD)") (class "Default")
      (node (ref "R16") (pin "2") (pinfunction "2_2") (pintype "passive"))
      (node (ref "U2") (pin "8") (pinfunction "TD_8") (pintype "passive"))
    )
    (net (code "28") (name "Net-(U2-VPWM)") (class "Default")
      (node (ref "R22") (pin "1") (pinfunction "1_1") (pintype "passive"))
      (node (ref "U2") (pin "3") (pinfunction "VPWM_3") (pintype "passive"))
    )
    (net (code "29") (name "VCC_IN") (class "Default")
      (node (ref "C1") (pin "1") (pinfunction "1_1") (pintype "passive"))
      (node (ref "C11") (pin "1") (pinfunction "1_1") (pintype "passive"))
      (node (ref "C14") (pin "1") (pinfunction "1_1") (pintype "passive"))
      (node (ref "C15") (pin "1") (pinfunction "1_1") (pintype "passive"))
      (node (ref "C16") (pin "1") (pinfunction "1_1") (pintype "passive"))
      (node (ref "C17") (pin "1") (pinfunction "1_1") (pintype "passive"))
      (node (ref "C2") (pin "1") (pinfunction "1_1") (pintype "passive"))
      (node (ref "C20") (pin "1") (pinfunction "1_1") (pintype "passive"))
      (node (ref "C25") (pin "2") (pinfunction "2_2") (pintype "passive"))
      (node (ref "C32") (pin "1") (pinfunction "1_1") (pintype "passive"))
      (node (ref "C4") (pin "1") (pinfunction "1_1") (pintype "passive"))
      (node (ref "C9") (pin "1") (pinfunction "1_1") (pintype "passive"))
      (node (ref "R7") (pin "2") (pinfunction "2_2") (pintype "passive"))
      (node (ref "R8") (pin "2") (pinfunction "2_2") (pintype "passive"))
      (node (ref "U2") (pin "30") (pinfunction "VIN_30") (pintype "passive"))
      (node (ref "U5") (pin "2") (pinfunction "2_2") (pintype "passive"))
    )
    (net (code "30") (name "VCC_OUT1") (class "Default")
      (node (ref "C13") (pin "1") (pinfunction "1_1") (pintype "passive"))
      (node (ref "C22") (pin "2") (pinfunction "2_2") (pintype "passive"))
      (node (ref "C26") (pin "1") (pinfunction "1_1") (pintype "passive"))
      (node (ref "P1") (pin "2") (pinfunction "2_2") (pintype "passive"))
      (node (ref "R13") (pin "1") (pinfunction "1_1") (pintype "passive"))
      (node (ref "R4") (pin "2") (pinfunction "2_2") (pintype "passive"))
      (node (ref "R5") (pin "2") (pinfunction "2_2") (pintype "passive"))
      (node (ref "U2") (pin "19") (pinfunction "VOUT_19") (pintype "passive"))
    )
  )
)
